# Circuito.net
KiCad netlist of a schematic drawn in EAGLE
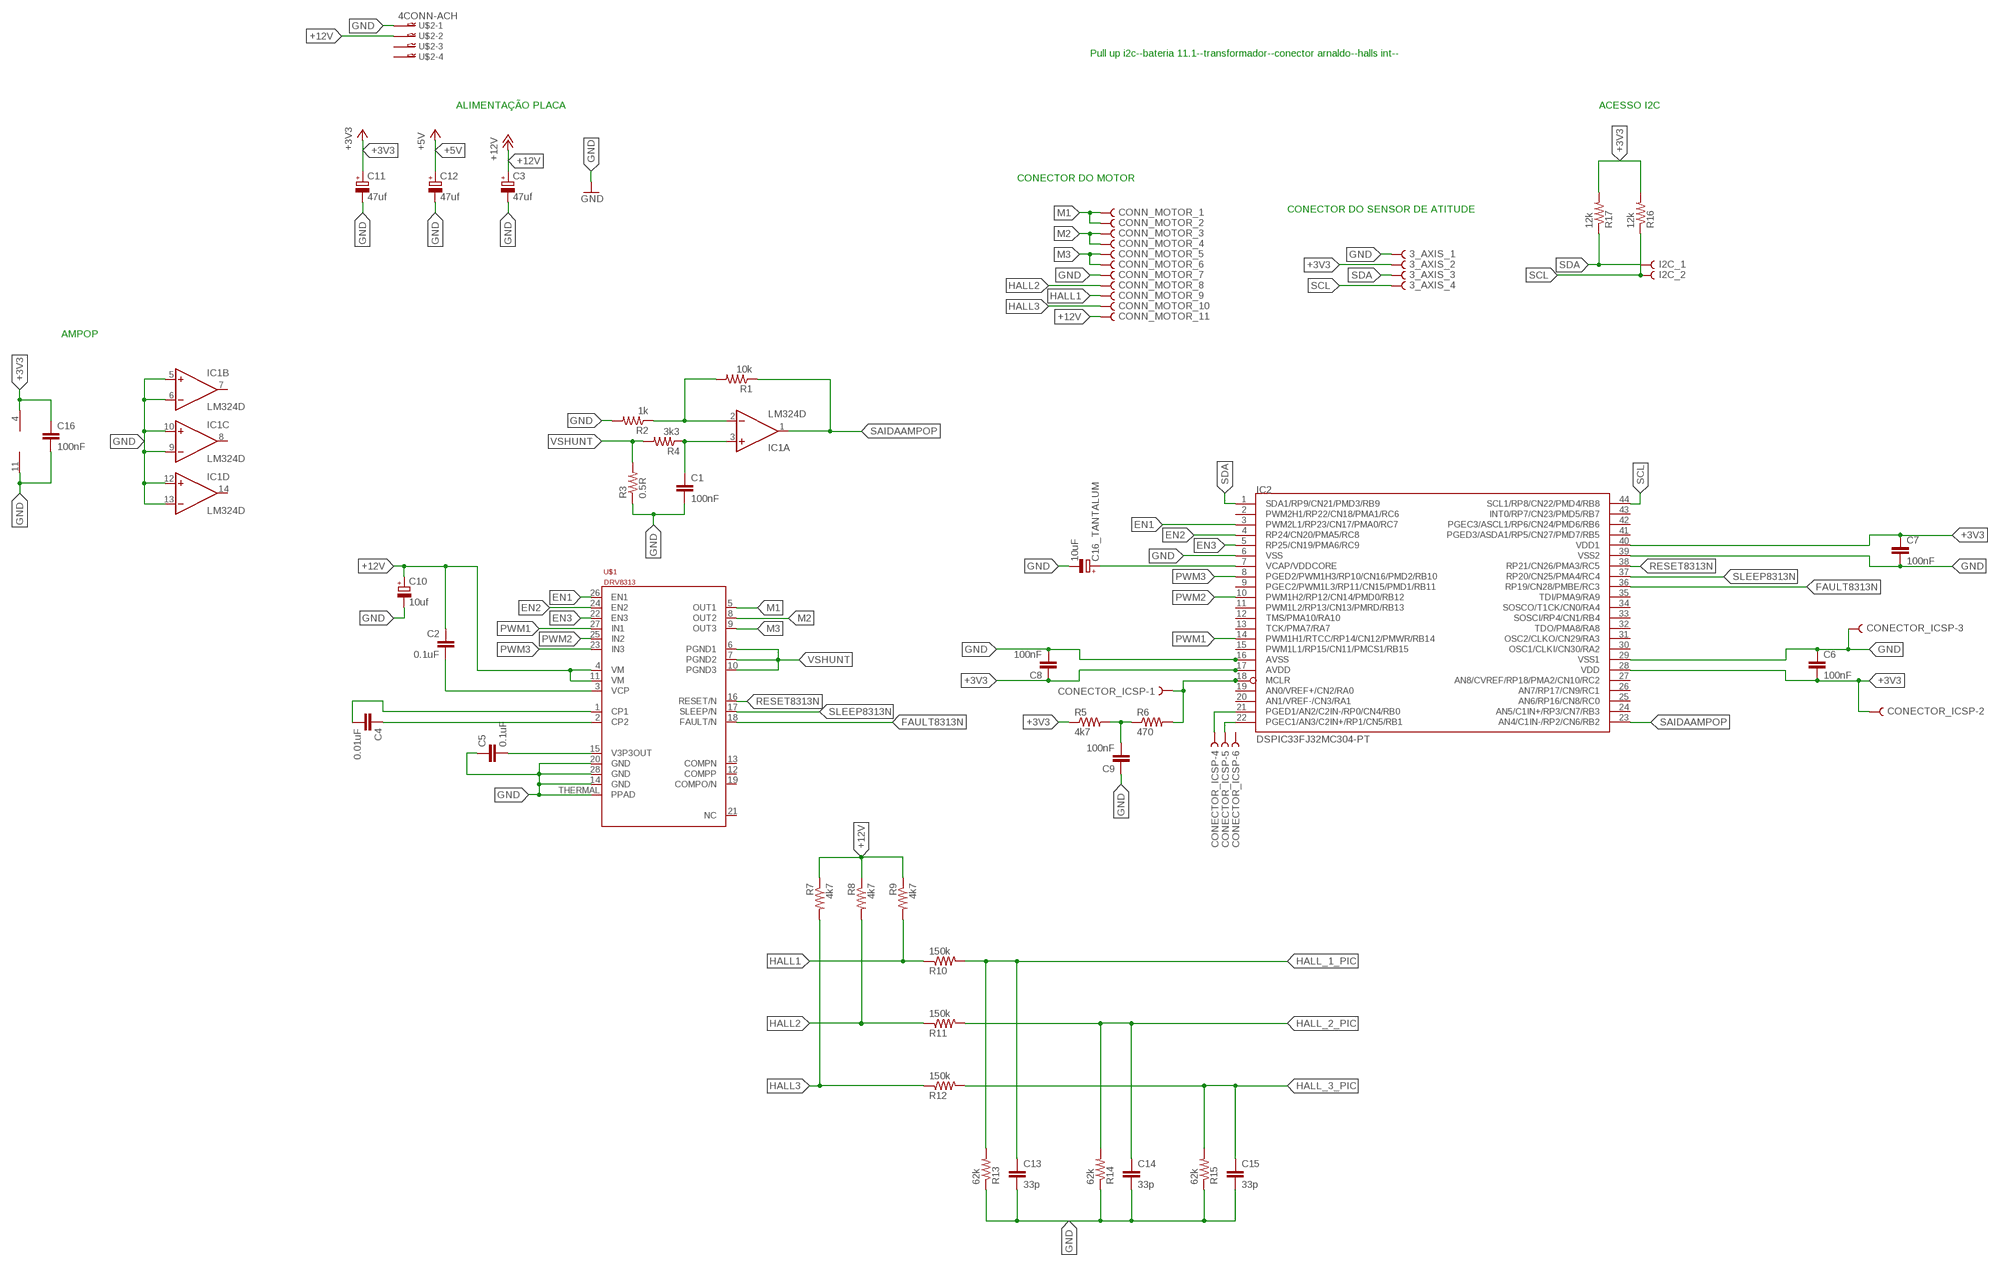
[diagram p0: schematic, sheet 1]

(export (version "E")
  (design (tool "Eeschema 10.0.6"))
  (components
    (comp (ref "3_AXIS_")
      (value "1_ROW-4_PINS-2.54MM")
      (footprint "eagle-import:1_ROW-4_PINS")
      (libsource (lib "eagle-import") (part "1_ROW-4_PINS-2.54MM"))
    )
    (comp (ref "C1")
      (value "100nF")
      (footprint "eagle-import:C1206")
      (libsource (lib "eagle-import") (part "resistor_C-EUC1206"))
    )
    (comp (ref "C2")
      (value "0.1uF")
      (footprint "eagle-import:C0805")
      (libsource (lib "eagle-import") (part "C-EUC0805"))
    )
    (comp (ref "C3")
      (value "47uf")
      (footprint "eagle-import:153CLV-0505")
      (libsource (lib "eagle-import") (part "CPOL-EU153CLV-0505"))
    )
    (comp (ref "C4")
      (value "0.01uF")
      (footprint "eagle-import:C0805")
      (libsource (lib "eagle-import") (part "C-EUC0805"))
    )
    (comp (ref "C5")
      (value "0.1uF")
      (footprint "eagle-import:C0805")
      (libsource (lib "eagle-import") (part "C-EUC0805"))
    )
    (comp (ref "C6")
      (value "100nF")
      (footprint "eagle-import:C0805")
      (libsource (lib "eagle-import") (part "C-EUC0805"))
    )
    (comp (ref "C7")
      (value "100nF")
      (footprint "eagle-import:C0805")
      (libsource (lib "eagle-import") (part "C-EUC0805"))
    )
    (comp (ref "C8")
      (value "100nF")
      (footprint "eagle-import:C0805")
      (libsource (lib "eagle-import") (part "C-EUC0805"))
    )
    (comp (ref "C9")
      (value "100nF")
      (footprint "eagle-import:C0805")
      (libsource (lib "eagle-import") (part "C-EUC0805"))
    )
    (comp (ref "C10")
      (value "10uf")
      (footprint "eagle-import:153CLV-0505")
      (libsource (lib "eagle-import") (part "CPOL-EU153CLV-0505"))
    )
    (comp (ref "C11")
      (value "47uf")
      (footprint "eagle-import:153CLV-0505")
      (libsource (lib "eagle-import") (part "CPOL-EU153CLV-0505"))
    )
    (comp (ref "C12")
      (value "47uf")
      (footprint "eagle-import:153CLV-0505")
      (libsource (lib "eagle-import") (part "CPOL-EU153CLV-0505"))
    )
    (comp (ref "C13")
      (value "33p")
      (footprint "eagle-import:C0603")
      (libsource (lib "eagle-import") (part "C-EUC0603"))
    )
    (comp (ref "C14")
      (value "33p")
      (footprint "eagle-import:C0603")
      (libsource (lib "eagle-import") (part "C-EUC0603"))
    )
    (comp (ref "C15")
      (value "33p")
      (footprint "eagle-import:C0603")
      (libsource (lib "eagle-import") (part "C-EUC0603"))
    )
    (comp (ref "C16")
      (value "100nF")
      (footprint "eagle-import:C1206")
      (libsource (lib "eagle-import") (part "resistor_C-EUC1206"))
    )
    (comp (ref "C16_TANTALUM")
      (value "10uF")
      (footprint "eagle-import:SMC_C")
      (libsource (lib "eagle-import") (part "CPOL-EUSMCC"))
    )
    (comp (ref "CONECTOR_ICSP-")
      (value "1_ROW-6_PINS-2.54MM")
      (footprint "eagle-import:1_ROW-6_PINS")
      (libsource (lib "eagle-import") (part "1_ROW-6_PINS-2.54MM"))
    )
    (comp (ref "CONN_MOTOR_")
      (value "1-84953-1")
      (footprint "eagle-import:1-84953-1")
      (libsource (lib "eagle-import") (part "1-84953-1"))
    )
    (comp (ref "I2C_")
      (value "1_ROW-2_PINS-2.54MM")
      (footprint "eagle-import:1_ROW-2_PINS")
      (libsource (lib "eagle-import") (part "1_ROW-2_PINS-2.54MM"))
    )
    (comp (ref "IC1")
      (value "LM324D")
      (footprint "eagle-import:SO14")
      (libsource (lib "eagle-import") (part "LM324D"))
    )
    (comp (ref "IC2")
      (value "DSPIC33FJ32MC304-PT")
      (footprint "eagle-import:TQFP44")
      (libsource (lib "eagle-import") (part "DSPIC33FJ32MC304-PT"))
    )
    (comp (ref "R1")
      (value "10k")
      (footprint "eagle-import:M1206")
      (libsource (lib "eagle-import") (part "resistor_R-US_M1206"))
    )
    (comp (ref "R2")
      (value "1k")
      (footprint "eagle-import:M1206")
      (libsource (lib "eagle-import") (part "resistor_R-US_M1206"))
    )
    (comp (ref "R3")
      (value "0.5R")
      (footprint "eagle-import:M1206")
      (libsource (lib "eagle-import") (part "resistor_R-US_M1206"))
    )
    (comp (ref "R4")
      (value "3k3")
      (footprint "eagle-import:M1206")
      (libsource (lib "eagle-import") (part "resistor_R-US_M1206"))
    )
    (comp (ref "R5")
      (value "4k7")
      (footprint "eagle-import:M1206")
      (libsource (lib "eagle-import") (part "resistor_R-US_M1206"))
    )
    (comp (ref "R6")
      (value "470")
      (footprint "eagle-import:M1206")
      (libsource (lib "eagle-import") (part "resistor_R-US_M1206"))
    )
    (comp (ref "R7")
      (value "4k7")
      (footprint "eagle-import:M0805")
      (libsource (lib "eagle-import") (part "R-US_M0805"))
    )
    (comp (ref "R8")
      (value "4k7")
      (footprint "eagle-import:M0805")
      (libsource (lib "eagle-import") (part "R-US_M0805"))
    )
    (comp (ref "R9")
      (value "4k7")
      (footprint "eagle-import:M0805")
      (libsource (lib "eagle-import") (part "R-US_M0805"))
    )
    (comp (ref "R10")
      (value "150k")
      (footprint "eagle-import:M0805")
      (libsource (lib "eagle-import") (part "R-US_M0805"))
    )
    (comp (ref "R11")
      (value "150k")
      (footprint "eagle-import:M0805")
      (libsource (lib "eagle-import") (part "R-US_M0805"))
    )
    (comp (ref "R12")
      (value "150k")
      (footprint "eagle-import:M0805")
      (libsource (lib "eagle-import") (part "R-US_M0805"))
    )
    (comp (ref "R13")
      (value "62k")
      (footprint "eagle-import:M0805")
      (libsource (lib "eagle-import") (part "R-US_M0805"))
    )
    (comp (ref "R14")
      (value "62k")
      (footprint "eagle-import:M0805")
      (libsource (lib "eagle-import") (part "R-US_M0805"))
    )
    (comp (ref "R15")
      (value "62k")
      (footprint "eagle-import:M0805")
      (libsource (lib "eagle-import") (part "R-US_M0805"))
    )
    (comp (ref "R16")
      (value "12k")
      (footprint "eagle-import:M0805")
      (libsource (lib "eagle-import") (part "R-US_M0805"))
    )
    (comp (ref "R17")
      (value "12k")
      (footprint "eagle-import:M0805")
      (libsource (lib "eagle-import") (part "R-US_M0805"))
    )
    (comp (ref "U$1")
      (value "DRV8811PWP/R")
      (footprint "eagle-import:HTSSOP28")
      (fields (field (name "MF") "TEXAS INSTRUMENTS"))
      (libsource (lib "eagle-import") (part "DRV8811PWP/R"))
    )
    (comp (ref "U$2")
      (value "4CONN-ACH")
      (footprint "eagle-import:4CONN-ACH")
      (libsource (lib "eagle-import") (part "4CONN-ACH"))
    )
  )
  (nets
    (net (code "1") (name "+3V3") (class "Default")
      (node (ref "3_AXIS_") (pin "2") (pinfunction "B_2") (pintype "passive"))
      (node (ref "C11") (pin "+") (pinfunction "+_+") (pintype "passive"))
      (node (ref "C16") (pin "1") (pinfunction "1_1") (pintype "passive"))
      (node (ref "C6") (pin "2") (pinfunction "2_2") (pintype "passive"))
      (node (ref "C7") (pin "1") (pinfunction "1_1") (pintype "passive"))
      (node (ref "C8") (pin "1") (pinfunction "1_1") (pintype "passive"))
      (node (ref "CONECTOR_ICSP-") (pin "1") (pinfunction "B_1") (pintype "passive"))
      (node (ref "CONECTOR_ICSP-") (pin "2") (pinfunction "B_2") (pintype "passive"))
      (node (ref "IC1") (pin "4") (pinfunction "V+_4") (pintype "power_in"))
      (node (ref "IC2") (pin "17") (pinfunction "AVDD_17") (pintype "power_in"))
      (node (ref "IC2") (pin "18") (pinfunction "MCLR_18") (pintype "input"))
      (node (ref "IC2") (pin "28") (pinfunction "VDD_28") (pintype "power_in"))
      (node (ref "IC2") (pin "40") (pinfunction "VDD1_40") (pintype "power_in"))
      (node (ref "R16") (pin "2") (pinfunction "2_2") (pintype "passive"))
      (node (ref "R17") (pin "2") (pinfunction "2_2") (pintype "passive"))
      (node (ref "R5") (pin "1") (pinfunction "1_1") (pintype "passive"))
      (node (ref "R6") (pin "2") (pinfunction "2_2") (pintype "passive"))
    )
    (net (code "2") (name "+5V") (class "Default")
      (node (ref "C12") (pin "+") (pinfunction "+_+") (pintype "passive"))
    )
    (net (code "3") (name "+12V") (class "Default")
      (node (ref "C10") (pin "+") (pinfunction "+_+") (pintype "passive"))
      (node (ref "C2") (pin "1") (pinfunction "1_1") (pintype "passive"))
      (node (ref "C3") (pin "+") (pinfunction "+_+") (pintype "passive"))
      (node (ref "CONN_MOTOR_") (pin "11") (pinfunction "CONN_FLAT_11") (pintype "passive"))
      (node (ref "R7") (pin "1") (pinfunction "1_1") (pintype "passive"))
      (node (ref "R8") (pin "1") (pinfunction "1_1") (pintype "passive"))
      (node (ref "R9") (pin "1") (pinfunction "1_1") (pintype "passive"))
      (node (ref "U$1") (pin "11") (pinfunction "VM_11") (pintype "output"))
      (node (ref "U$1") (pin "4") (pinfunction "VM_4") (pintype "output"))
      (node (ref "U$2") (pin "2") (pinfunction "1_2") (pintype "passive"))
    )
    (net (code "4") (name "/NC") (class "Default")
      (node (ref "U$1") (pin "21") (pinfunction "NC_21") (pintype "power_in"))
    )
    (net (code "5") (name "EN1") (class "Default")
      (node (ref "IC2") (pin "3") (pinfunction "PWM2L1/RP23/CN17/PMA0/RC7_3") (pintype "bidirectional"))
      (node (ref "U$1") (pin "26") (pinfunction "EN1_26") (pintype "input"))
    )
    (net (code "6") (name "EN2") (class "Default")
      (node (ref "IC2") (pin "4") (pinfunction "RP24/CN20/PMA5/RC8_4") (pintype "bidirectional"))
      (node (ref "U$1") (pin "24") (pinfunction "EN2_24") (pintype "bidirectional"))
    )
    (net (code "7") (name "EN3") (class "Default")
      (node (ref "IC2") (pin "5") (pinfunction "RP25/CN19/PMA6/RC9_5") (pintype "bidirectional"))
      (node (ref "U$1") (pin "22") (pinfunction "EN3_22") (pintype "bidirectional"))
    )
    (net (code "8") (name "FAULT8313N") (class "Default")
      (node (ref "IC2") (pin "36") (pinfunction "RP19/CN28/PMBE/RC3_36") (pintype "bidirectional"))
      (node (ref "U$1") (pin "18") (pinfunction "FAULT/N_18") (pintype "output"))
    )
    (net (code "9") (name "GND") (class "Default")
      (node (ref "3_AXIS_") (pin "1") (pinfunction "B_1") (pintype "passive"))
      (node (ref "C1") (pin "2") (pinfunction "2_2") (pintype "passive"))
      (node (ref "C10") (pin "-") (pinfunction "-_-") (pintype "passive"))
      (node (ref "C11") (pin "-") (pinfunction "-_-") (pintype "passive"))
      (node (ref "C12") (pin "-") (pinfunction "-_-") (pintype "passive"))
      (node (ref "C13") (pin "2") (pinfunction "2_2") (pintype "passive"))
      (node (ref "C14") (pin "2") (pinfunction "2_2") (pintype "passive"))
      (node (ref "C15") (pin "2") (pinfunction "2_2") (pintype "passive"))
      (node (ref "C16") (pin "2") (pinfunction "2_2") (pintype "passive"))
      (node (ref "C16_TANTALUM") (pin "-") (pinfunction "-_-") (pintype "passive"))
      (node (ref "C3") (pin "-") (pinfunction "-_-") (pintype "passive"))
      (node (ref "C5") (pin "1") (pinfunction "1_1") (pintype "passive"))
      (node (ref "C6") (pin "1") (pinfunction "1_1") (pintype "passive"))
      (node (ref "C7") (pin "2") (pinfunction "2_2") (pintype "passive"))
      (node (ref "C8") (pin "2") (pinfunction "2_2") (pintype "passive"))
      (node (ref "C9") (pin "1") (pinfunction "1_1") (pintype "passive"))
      (node (ref "CONECTOR_ICSP-") (pin "3") (pinfunction "B_3") (pintype "passive"))
      (node (ref "CONN_MOTOR_") (pin "7") (pinfunction "CONN_FLAT_7") (pintype "passive"))
      (node (ref "IC1") (pin "10") (pinfunction "+IN_10") (pintype "input"))
      (node (ref "IC1") (pin "11") (pinfunction "V-_11") (pintype "power_in"))
      (node (ref "IC1") (pin "12") (pinfunction "+IN_12") (pintype "input"))
      (node (ref "IC1") (pin "13") (pinfunction "-IN_13") (pintype "input"))
      (node (ref "IC1") (pin "5") (pinfunction "+IN_5") (pintype "input"))
      (node (ref "IC1") (pin "6") (pinfunction "-IN_6") (pintype "input"))
      (node (ref "IC1") (pin "9") (pinfunction "-IN_9") (pintype "input"))
      (node (ref "IC2") (pin "16") (pinfunction "AVSS_16") (pintype "power_in"))
      (node (ref "IC2") (pin "29") (pinfunction "VSS1_29") (pintype "power_in"))
      (node (ref "IC2") (pin "39") (pinfunction "VSS2_39") (pintype "power_in"))
      (node (ref "IC2") (pin "6") (pinfunction "VSS_6") (pintype "power_in"))
      (node (ref "R13") (pin "1") (pinfunction "1_1") (pintype "passive"))
      (node (ref "R14") (pin "1") (pinfunction "1_1") (pintype "passive"))
      (node (ref "R15") (pin "1") (pinfunction "1_1") (pintype "passive"))
      (node (ref "R2") (pin "2") (pinfunction "2_2") (pintype "passive"))
      (node (ref "R3") (pin "1") (pinfunction "1_1") (pintype "passive"))
      (node (ref "U$1") (pin "14") (pinfunction "GND_14") (pintype "power_in"))
      (node (ref "U$1") (pin "20") (pinfunction "GND_20") (pintype "bidirectional"))
      (node (ref "U$1") (pin "28") (pinfunction "GND_28") (pintype "power_in"))
      (node (ref "U$1") (pin "THERMAL") (pinfunction "PPAD_THERMAL") (pintype "power_in"))
      (node (ref "U$2") (pin "1") (pinfunction "1_1") (pintype "passive"))
    )
    (net (code "10") (name "HALL1") (class "Default")
      (node (ref "CONN_MOTOR_") (pin "9") (pinfunction "CONN_FLAT_9") (pintype "passive"))
      (node (ref "R10") (pin "1") (pinfunction "1_1") (pintype "passive"))
      (node (ref "R9") (pin "2") (pinfunction "2_2") (pintype "passive"))
    )
    (net (code "11") (name "HALL2") (class "Default")
      (node (ref "CONN_MOTOR_") (pin "8") (pinfunction "CONN_FLAT_8") (pintype "passive"))
      (node (ref "R11") (pin "1") (pinfunction "1_1") (pintype "passive"))
      (node (ref "R8") (pin "2") (pinfunction "2_2") (pintype "passive"))
    )
    (net (code "12") (name "HALL3") (class "Default")
      (node (ref "CONN_MOTOR_") (pin "10") (pinfunction "CONN_FLAT_10") (pintype "passive"))
      (node (ref "R12") (pin "1") (pinfunction "1_1") (pintype "passive"))
      (node (ref "R7") (pin "2") (pinfunction "2_2") (pintype "passive"))
    )
    (net (code "13") (name "HALL_1_PIC") (class "Default")
      (node (ref "C13") (pin "1") (pinfunction "1_1") (pintype "passive"))
      (node (ref "R10") (pin "2") (pinfunction "2_2") (pintype "passive"))
      (node (ref "R13") (pin "2") (pinfunction "2_2") (pintype "passive"))
    )
    (net (code "14") (name "HALL_2_PIC") (class "Default")
      (node (ref "C14") (pin "1") (pinfunction "1_1") (pintype "passive"))
      (node (ref "R11") (pin "2") (pinfunction "2_2") (pintype "passive"))
      (node (ref "R14") (pin "2") (pinfunction "2_2") (pintype "passive"))
    )
    (net (code "15") (name "HALL_3_PIC") (class "Default")
      (node (ref "C15") (pin "1") (pinfunction "1_1") (pintype "passive"))
      (node (ref "R12") (pin "2") (pinfunction "2_2") (pintype "passive"))
      (node (ref "R15") (pin "2") (pinfunction "2_2") (pintype "passive"))
    )
    (net (code "16") (name "M1") (class "Default")
      (node (ref "CONN_MOTOR_") (pin "1") (pinfunction "CONN_FLAT_1") (pintype "passive"))
      (node (ref "CONN_MOTOR_") (pin "2") (pinfunction "CONN_FLAT_2") (pintype "passive"))
      (node (ref "U$1") (pin "5") (pinfunction "OUT1_5") (pintype "input"))
    )
    (net (code "17") (name "M2") (class "Default")
      (node (ref "CONN_MOTOR_") (pin "3") (pinfunction "CONN_FLAT_3") (pintype "passive"))
      (node (ref "CONN_MOTOR_") (pin "4") (pinfunction "CONN_FLAT_4") (pintype "passive"))
      (node (ref "U$1") (pin "8") (pinfunction "OUT2_8") (pintype "input"))
    )
    (net (code "18") (name "M3") (class "Default")
      (node (ref "CONN_MOTOR_") (pin "5") (pinfunction "CONN_FLAT_5") (pintype "passive"))
      (node (ref "CONN_MOTOR_") (pin "6") (pinfunction "CONN_FLAT_6") (pintype "passive"))
      (node (ref "U$1") (pin "9") (pinfunction "OUT3_9") (pintype "input"))
    )
    (net (code "19") (name "Net-(C9-Pad2)") (class "Default")
      (node (ref "C9") (pin "2") (pinfunction "2_2") (pintype "passive"))
      (node (ref "R5") (pin "2") (pinfunction "2_2") (pintype "passive"))
      (node (ref "R6") (pin "1") (pinfunction "1_1") (pintype "passive"))
    )
    (net (code "20") (name "Net-(CONECTOR_ICSP-D-B)") (class "Default")
      (node (ref "CONECTOR_ICSP-") (pin "4") (pinfunction "B_4") (pintype "passive"))
      (node (ref "IC2") (pin "21") (pinfunction "PGED1/AN2/C2IN-/RP0/CN4/RB0_21") (pintype "bidirectional"))
    )
    (net (code "21") (name "Net-(CONECTOR_ICSP-E-B)") (class "Default")
      (node (ref "CONECTOR_ICSP-") (pin "5") (pinfunction "B_5") (pintype "passive"))
      (node (ref "IC2") (pin "22") (pinfunction "PGEC1/AN3/C2IN+/RP1/CN5/RB1_22") (pintype "bidirectional"))
    )
    (net (code "22") (name "Net-(IC1A--IN)") (class "Default")
      (node (ref "IC1") (pin "2") (pinfunction "-IN_2") (pintype "input"))
      (node (ref "R1") (pin "2") (pinfunction "2_2") (pintype "passive"))
      (node (ref "R2") (pin "1") (pinfunction "1_1") (pintype "passive"))
    )
    (net (code "23") (name "Net-(IC2-VCAP{slash}VDDCORE)") (class "Default")
      (node (ref "C16_TANTALUM") (pin "+") (pinfunction "+_+") (pintype "passive"))
      (node (ref "IC2") (pin "7") (pinfunction "VCAP/VDDCORE_7") (pintype "power_in"))
    )
    (net (code "24") (name "Net-(U$1-CP1)") (class "Default")
      (node (ref "C4") (pin "2") (pinfunction "2_2") (pintype "passive"))
      (node (ref "U$1") (pin "1") (pinfunction "CP1_1") (pintype "power_in"))
    )
    (net (code "25") (name "Net-(U$1-CP2)") (class "Default")
      (node (ref "C4") (pin "1") (pinfunction "1_1") (pintype "passive"))
      (node (ref "U$1") (pin "2") (pinfunction "CP2_2") (pintype "output"))
    )
    (net (code "26") (name "Net-(U$1-V3P3OUT)") (class "Default")
      (node (ref "C5") (pin "2") (pinfunction "2_2") (pintype "passive"))
      (node (ref "U$1") (pin "15") (pinfunction "V3P3OUT_15") (pintype "power_in"))
    )
    (net (code "27") (name "Net-(U$1-VCP)") (class "Default")
      (node (ref "C2") (pin "2") (pinfunction "2_2") (pintype "passive"))
      (node (ref "U$1") (pin "3") (pinfunction "VCP_3") (pintype "input"))
    )
    (net (code "28") (name "PWM1") (class "Default")
      (node (ref "IC2") (pin "14") (pinfunction "PWM1H1/RTCC/RP14/CN12/PMWR/RB14_14") (pintype "bidirectional"))
      (node (ref "U$1") (pin "27") (pinfunction "IN1_27") (pintype "input"))
    )
    (net (code "29") (name "PWM2") (class "Default")
      (node (ref "IC2") (pin "10") (pinfunction "PWM1H2/RP12/CN14/PMD0/RB12_10") (pintype "bidirectional"))
      (node (ref "U$1") (pin "25") (pinfunction "IN2_25") (pintype "output"))
    )
    (net (code "30") (name "PWM3") (class "Default")
      (node (ref "IC2") (pin "8") (pinfunction "PGED2/PWM1H3/RP10/CN16/PMD2/RB10_8") (pintype "bidirectional"))
      (node (ref "U$1") (pin "23") (pinfunction "IN3_23") (pintype "bidirectional"))
    )
    (net (code "31") (name "RESET8313N") (class "Default")
      (node (ref "IC2") (pin "38") (pinfunction "RP21/CN26/PMA3/RC5_38") (pintype "bidirectional"))
      (node (ref "U$1") (pin "16") (pinfunction "RESET/N_16") (pintype "input"))
    )
    (net (code "32") (name "SAIDAAMPOP") (class "Default")
      (node (ref "IC1") (pin "1") (pinfunction "OUT_1") (pintype "output"))
      (node (ref "IC2") (pin "23") (pinfunction "AN4/C1IN-/RP2/CN6/RB2_23") (pintype "bidirectional"))
      (node (ref "R1") (pin "1") (pinfunction "1_1") (pintype "passive"))
    )
    (net (code "33") (name "SCL") (class "Default")
      (node (ref "3_AXIS_") (pin "4") (pinfunction "B_4") (pintype "passive"))
      (node (ref "I2C_") (pin "2") (pinfunction "B_2") (pintype "passive"))
      (node (ref "IC2") (pin "44") (pinfunction "SCL1/RP8/CN22/PMD4/RB8_44") (pintype "bidirectional"))
      (node (ref "R16") (pin "1") (pinfunction "1_1") (pintype "passive"))
    )
    (net (code "34") (name "SDA") (class "Default")
      (node (ref "3_AXIS_") (pin "3") (pinfunction "B_3") (pintype "passive"))
      (node (ref "I2C_") (pin "1") (pinfunction "B_1") (pintype "passive"))
      (node (ref "IC2") (pin "1") (pinfunction "SDA1/RP9/CN21/PMD3/RB9_1") (pintype "bidirectional"))
      (node (ref "R17") (pin "1") (pinfunction "1_1") (pintype "passive"))
    )
    (net (code "35") (name "SLEEP8313N") (class "Default")
      (node (ref "IC2") (pin "37") (pinfunction "RP20/CN25/PMA4/RC4_37") (pintype "bidirectional"))
      (node (ref "U$1") (pin "17") (pinfunction "SLEEP/N_17") (pintype "input"))
    )
    (net (code "36") (name "VSHUNT") (class "Default")
      (node (ref "C1") (pin "1") (pinfunction "1_1") (pintype "passive"))
      (node (ref "IC1") (pin "3") (pinfunction "+IN_3") (pintype "input"))
      (node (ref "R3") (pin "2") (pinfunction "2_2") (pintype "passive"))
      (node (ref "R4") (pin "1") (pinfunction "1_1") (pintype "passive"))
      (node (ref "R4") (pin "2") (pinfunction "2_2") (pintype "passive"))
      (node (ref "U$1") (pin "10") (pinfunction "PGND3_10") (pintype "power_in"))
      (node (ref "U$1") (pin "6") (pinfunction "PGND1_6") (pintype "input"))
      (node (ref "U$1") (pin "7") (pinfunction "PGND2_7") (pintype "power_in"))
    )
    (net (code "37") (name "unconnected-(CONECTOR_ICSP-F-B-Pad6)") (class "Default")
      (node (ref "CONECTOR_ICSP-") (pin "6") (pinfunction "B_6") (pintype "passive"))
    )
    (net (code "38") (name "unconnected-(IC1B-OUT-Pad7)") (class "Default")
      (node (ref "IC1") (pin "7") (pinfunction "OUT_7") (pintype "output"))
    )
    (net (code "39") (name "unconnected-(IC1C-OUT-Pad8)") (class "Default")
      (node (ref "IC1") (pin "8") (pinfunction "OUT_8") (pintype "output"))
    )
    (net (code "40") (name "unconnected-(IC1D-OUT-Pad14)") (class "Default")
      (node (ref "IC1") (pin "14") (pinfunction "OUT_14") (pintype "output"))
    )
    (net (code "41") (name "unconnected-(IC2-AN0{slash}VREF+{slash}CN2{slash}RA0-Pad19)") (class "Default")
      (node (ref "IC2") (pin "19") (pinfunction "AN0/VREF+/CN2/RA0_19") (pintype "bidirectional"))
    )
    (net (code "42") (name "unconnected-(IC2-AN1{slash}VREF-{slash}CN3{slash}RA1-Pad20)") (class "Default")
      (node (ref "IC2") (pin "20") (pinfunction "AN1/VREF-/CN3/RA1_20") (pintype "bidirectional"))
    )
    (net (code "43") (name "unconnected-(IC2-AN5{slash}C1IN+{slash}RP3{slash}CN7{slash}RB3-Pad24)") (class "Default")
      (node (ref "IC2") (pin "24") (pinfunction "AN5/C1IN+/RP3/CN7/RB3_24") (pintype "bidirectional"))
    )
    (net (code "44") (name "unconnected-(IC2-AN6{slash}RP16{slash}CN8{slash}RC0-Pad25)") (class "Default")
      (node (ref "IC2") (pin "25") (pinfunction "AN6/RP16/CN8/RC0_25") (pintype "bidirectional"))
    )
    (net (code "45") (name "unconnected-(IC2-AN7{slash}RP17{slash}CN9{slash}RC1-Pad26)") (class "Default")
      (node (ref "IC2") (pin "26") (pinfunction "AN7/RP17/CN9/RC1_26") (pintype "bidirectional"))
    )
    (net (code "46") (name "unconnected-(IC2-AN8{slash}CVREF{slash}RP18{slash}PMA2{slash}CN10{slash}RC2-Pad27)") (class "Default")
      (node (ref "IC2") (pin "27") (pinfunction "AN8/CVREF/RP18/PMA2/CN10/RC2_27") (pintype "bidirectional"))
    )
    (net (code "47") (name "unconnected-(IC2-INT0{slash}RP7{slash}CN23{slash}PMD5{slash}RB7-Pad43)") (class "Default")
      (node (ref "IC2") (pin "43") (pinfunction "INT0/RP7/CN23/PMD5/RB7_43") (pintype "bidirectional"))
    )
    (net (code "48") (name "unconnected-(IC2-OSC1{slash}CLKI{slash}CN30{slash}RA2-Pad30)") (class "Default")
      (node (ref "IC2") (pin "30") (pinfunction "OSC1/CLKI/CN30/RA2_30") (pintype "bidirectional"))
    )
    (net (code "49") (name "unconnected-(IC2-OSC2{slash}CLKO{slash}CN29{slash}RA3-Pad31)") (class "Default")
      (node (ref "IC2") (pin "31") (pinfunction "OSC2/CLKO/CN29/RA3_31") (pintype "bidirectional"))
    )
    (net (code "50") (name "unconnected-(IC2-PGEC2{slash}PWM1L3{slash}RP11{slash}CN15{slash}PMD1{slash}RB11-Pad9)") (class "Default")
      (node (ref "IC2") (pin "9") (pinfunction "PGEC2/PWM1L3/RP11/CN15/PMD1/RB11_9") (pintype "bidirectional"))
    )
    (net (code "51") (name "unconnected-(IC2-PGEC3{slash}ASCL1{slash}RP6{slash}CN24{slash}PMD6{slash}RB6-Pad42)") (class "Default")
      (node (ref "IC2") (pin "42") (pinfunction "PGEC3/ASCL1/RP6/CN24/PMD6/RB6_42") (pintype "bidirectional"))
    )
    (net (code "52") (name "unconnected-(IC2-PGED3{slash}ASDA1{slash}RP5{slash}CN27{slash}PMD7{slash}RB5-Pad41)") (class "Default")
      (node (ref "IC2") (pin "41") (pinfunction "PGED3/ASDA1/RP5/CN27/PMD7/RB5_41") (pintype "bidirectional"))
    )
    (net (code "53") (name "unconnected-(IC2-PWM1L1{slash}RP15{slash}CN11{slash}PMCS1{slash}RB15-Pad15)") (class "Default")
      (node (ref "IC2") (pin "15") (pinfunction "PWM1L1/RP15/CN11/PMCS1/RB15_15") (pintype "bidirectional"))
    )
    (net (code "54") (name "unconnected-(IC2-PWM1L2{slash}RP13{slash}CN13{slash}PMRD{slash}RB13-Pad11)") (class "Default")
      (node (ref "IC2") (pin "11") (pinfunction "PWM1L2/RP13/CN13/PMRD/RB13_11") (pintype "bidirectional"))
    )
    (net (code "55") (name "unconnected-(IC2-PWM2H1{slash}RP22{slash}CN18{slash}PMA1{slash}RC6-Pad2)") (class "Default")
      (node (ref "IC2") (pin "2") (pinfunction "PWM2H1/RP22/CN18/PMA1/RC6_2") (pintype "bidirectional"))
    )
    (net (code "56") (name "unconnected-(IC2-SOSCI{slash}RP4{slash}CN1{slash}RB4-Pad33)") (class "Default")
      (node (ref "IC2") (pin "33") (pinfunction "SOSCI/RP4/CN1/RB4_33") (pintype "bidirectional"))
    )
    (net (code "57") (name "unconnected-(IC2-SOSCO{slash}T1CK{slash}CN0{slash}RA4-Pad34)") (class "Default")
      (node (ref "IC2") (pin "34") (pinfunction "SOSCO/T1CK/CN0/RA4_34") (pintype "bidirectional"))
    )
    (net (code "58") (name "unconnected-(IC2-TCK{slash}PMA7{slash}RA7-Pad13)") (class "Default")
      (node (ref "IC2") (pin "13") (pinfunction "TCK/PMA7/RA7_13") (pintype "bidirectional"))
    )
    (net (code "59") (name "unconnected-(IC2-TDI{slash}PMA9{slash}RA9-Pad35)") (class "Default")
      (node (ref "IC2") (pin "35") (pinfunction "TDI/PMA9/RA9_35") (pintype "bidirectional"))
    )
    (net (code "60") (name "unconnected-(IC2-TDO{slash}PMA8{slash}RA8-Pad32)") (class "Default")
      (node (ref "IC2") (pin "32") (pinfunction "TDO/PMA8/RA8_32") (pintype "bidirectional"))
    )
    (net (code "61") (name "unconnected-(IC2-TMS{slash}PMA10{slash}RA10-Pad12)") (class "Default")
      (node (ref "IC2") (pin "12") (pinfunction "TMS/PMA10/RA10_12") (pintype "bidirectional"))
    )
    (net (code "62") (name "unconnected-(U$1-COMPN-Pad13)") (class "Default")
      (node (ref "U$1") (pin "13") (pinfunction "COMPN_13") (pintype "input"))
    )
    (net (code "63") (name "unconnected-(U$1-COMPO{slash}N-Pad19)") (class "Default")
      (node (ref "U$1") (pin "19") (pinfunction "COMPO/N_19") (pintype "input"))
    )
    (net (code "64") (name "unconnected-(U$1-COMPP-Pad12)") (class "Default")
      (node (ref "U$1") (pin "12") (pinfunction "COMPP_12") (pintype "input"))
    )
    (net (code "65") (name "unconnected-(U$2C-1-Pad3)") (class "Default")
      (node (ref "U$2") (pin "3") (pinfunction "1_3") (pintype "passive"))
    )
    (net (code "66") (name "unconnected-(U$2D-1-Pad4)") (class "Default")
      (node (ref "U$2") (pin "4") (pinfunction "1_4") (pintype "passive"))
    )
  )
)
